# RP_INTERFACE_BOARD_V1.net
KiCad netlist of a schematic drawn in Altium Designer
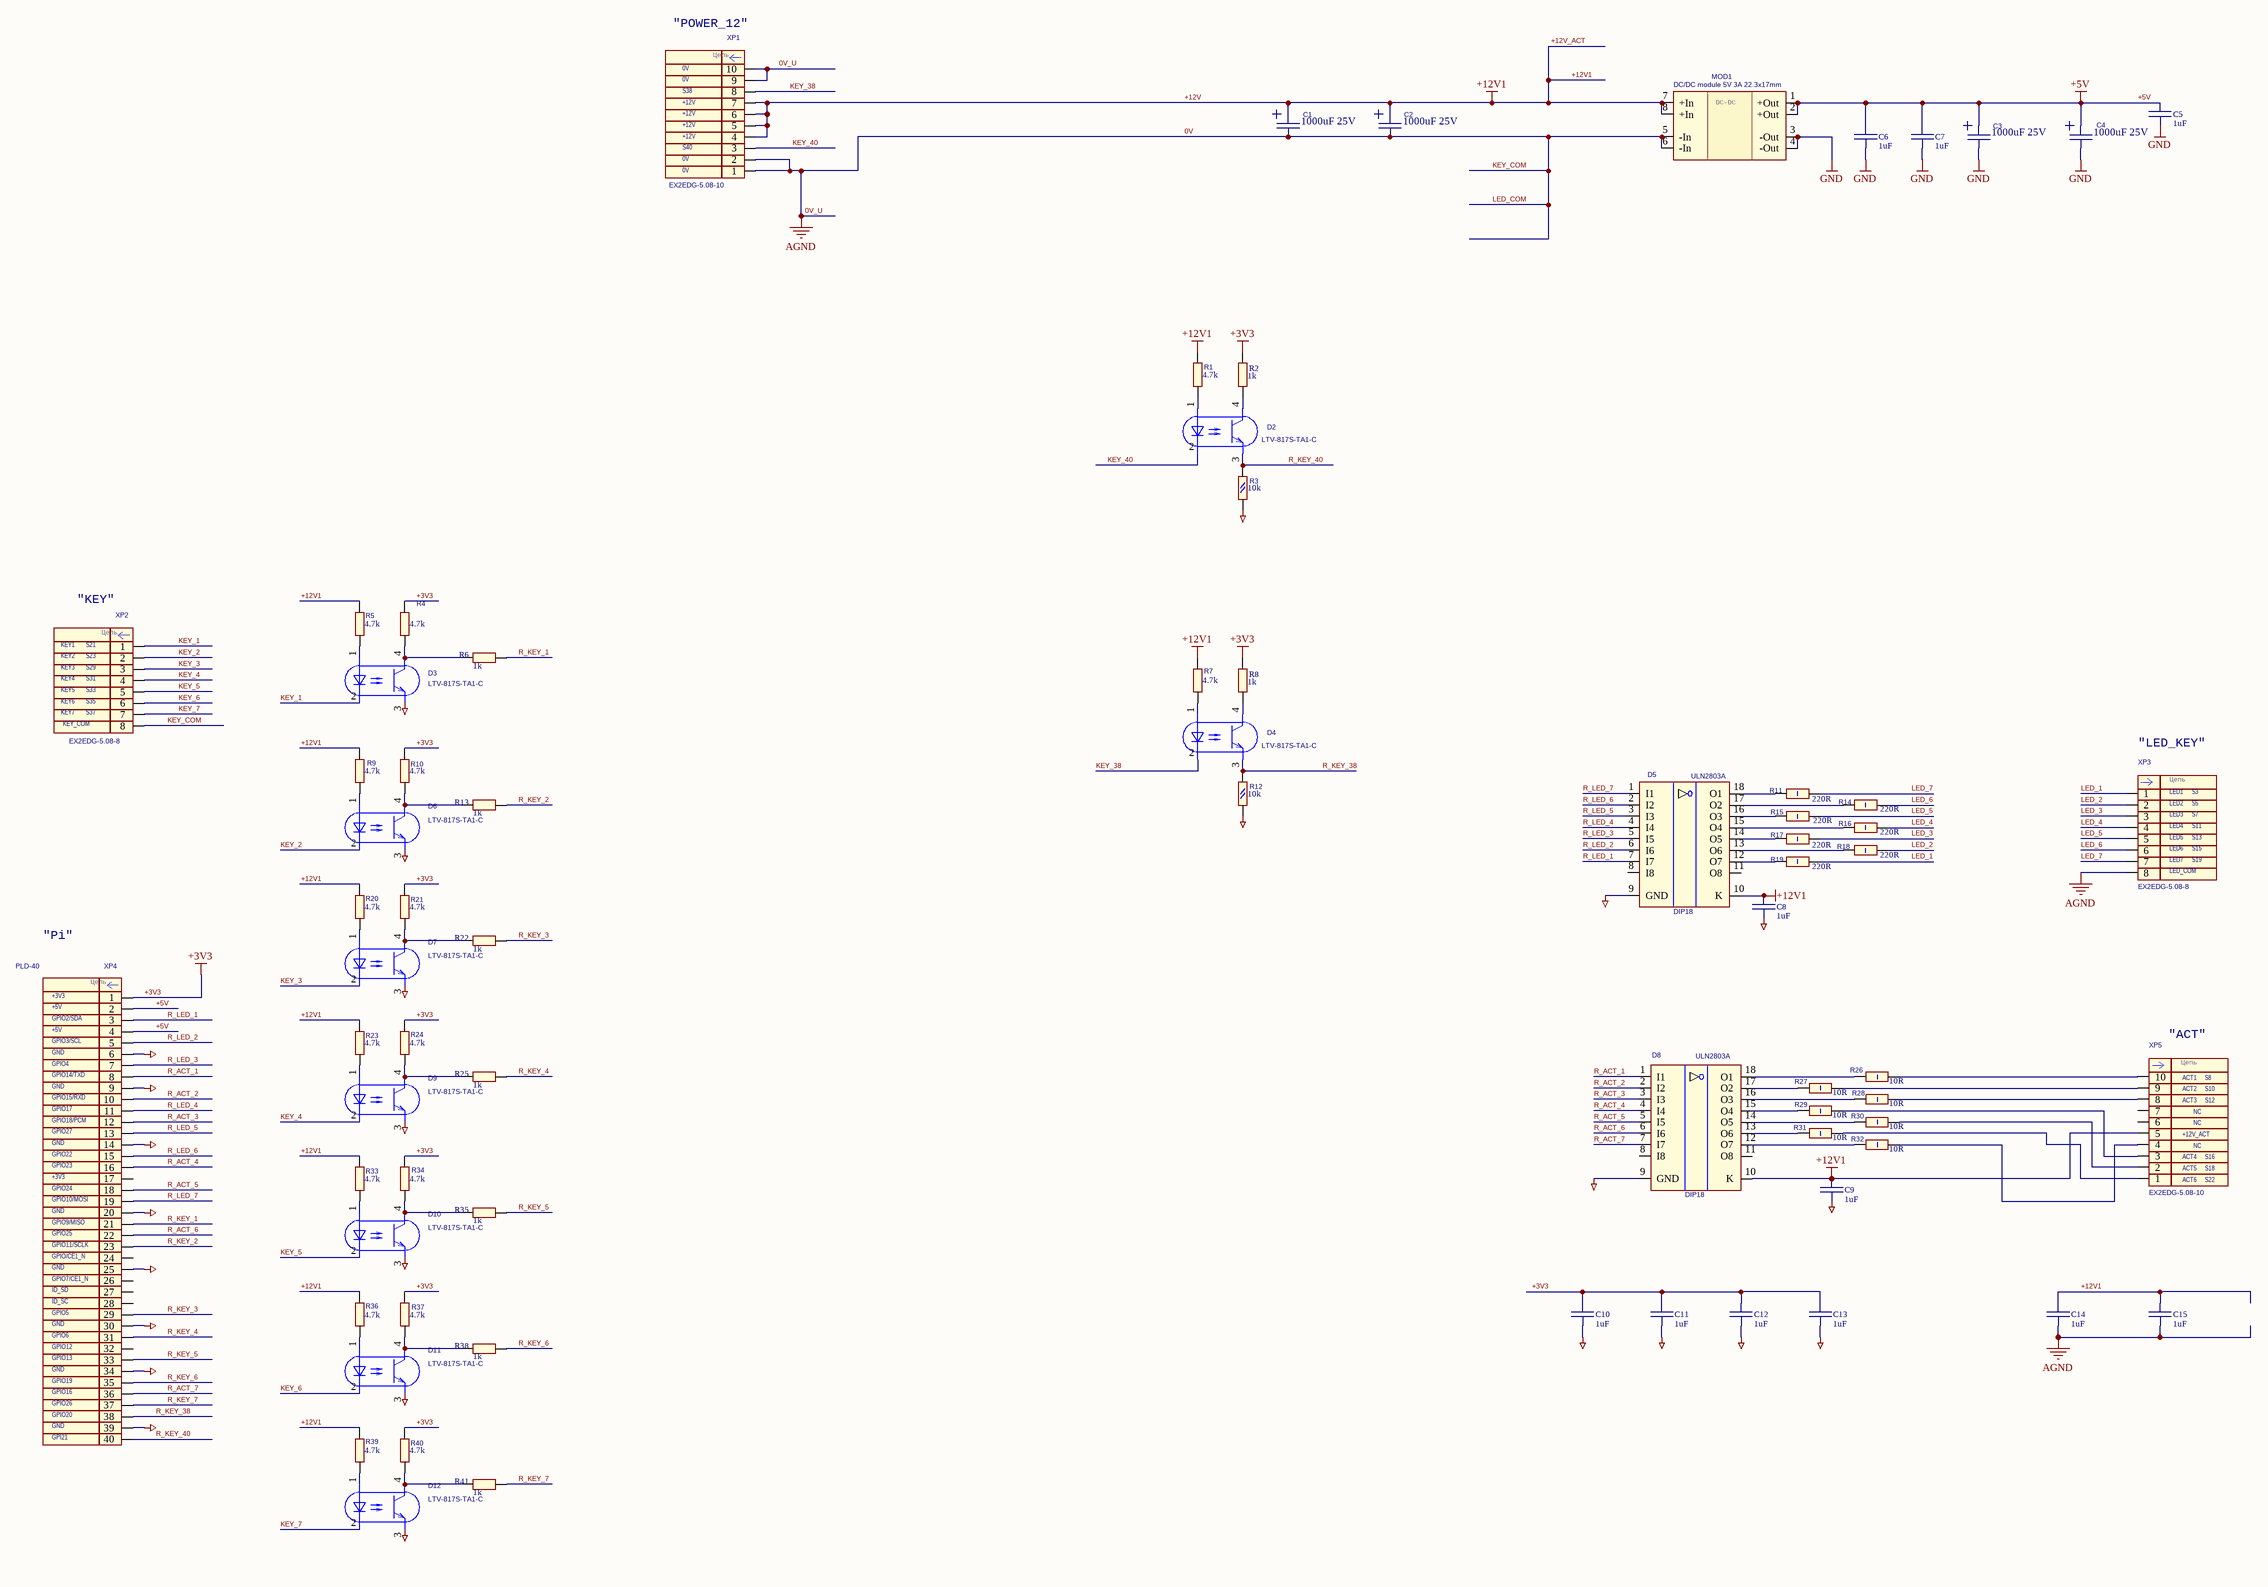
[diagram p0: RP_INTERFACE_BOARD_V1.SchDoc]

(export (version "E")
  (design (tool "Eeschema 10.0.6"))
  (components
    (comp (ref "C1")
      (value "EXR102M25B")
      (footprint "RADIAL 13X25")
      (description "1000uF 25V 13x21mm")
      (fields (field (name "ALTIUM_UNNAMED_1") "1000uF 25V"))
      (libsource (lib "*") (part "EXR102M25B"))
    )
    (comp (ref "C2")
      (value "EXR102M25B")
      (footprint "RADIAL 13X25")
      (description "1000uF 25V 13x21mm")
      (fields (field (name "ALTIUM_UNNAMED_1") "1000uF 25V"))
      (libsource (lib "RP_INTERFACE_BOARD") (part "EXR102M25B"))
    )
    (comp (ref "C3")
      (value "EXR102M25B")
      (footprint "RADIAL 13X25")
      (description "1000uF 25V 13x21mm")
      (fields (field (name "ALTIUM_UNNAMED_1") "1000uF 25V"))
      (libsource (lib "RP_INTERFACE_BOARD") (part "EXR102M25B"))
    )
    (comp (ref "C4")
      (value "EXR102M25B")
      (footprint "RADIAL 13X25")
      (description "1000uF 25V 13x21mm")
      (fields (field (name "ALTIUM_UNNAMED_1") "1000uF 25V"))
      (libsource (lib "RP_INTERFACE_BOARD") (part "EXR102M25B"))
    )
    (comp (ref "C5")
      (value "C0805, 1uF, 50V, X7R")
      (footprint "C0805")
      (fields (field (name "ALTIUM_UNNAMED_1") "1uF"))
      (libsource (lib "CAPACITORS") (part "C0805, 1uF, 50V, X7R"))
    )
    (comp (ref "C6")
      (value "C0805, 1uF, 50V, X7R")
      (footprint "C0805")
      (fields (field (name "ALTIUM_UNNAMED_1") "1uF"))
      (libsource (lib "CAPACITORS") (part "C0805, 1uF, 50V, X7R"))
    )
    (comp (ref "C7")
      (value "C0805, 1uF, 50V, X7R")
      (footprint "C0805")
      (fields (field (name "ALTIUM_UNNAMED_1") "1uF"))
      (libsource (lib "CAPACITORS") (part "C0805, 1uF, 50V, X7R"))
    )
    (comp (ref "C8")
      (value "C0805, 1uF, 50V, X7R")
      (footprint "C0805")
      (fields (field (name "ALTIUM_UNNAMED_1") "1uF"))
      (libsource (lib "CAPACITORS") (part "C0805, 1uF, 50V, X7R"))
    )
    (comp (ref "C9")
      (value "C0805, 1uF, 50V, X7R")
      (footprint "C0805")
      (fields (field (name "ALTIUM_UNNAMED_1") "1uF"))
      (libsource (lib "CAPACITORS") (part "C0805, 1uF, 50V, X7R"))
    )
    (comp (ref "C10")
      (value "C0805, 1uF, 50V, X7R")
      (footprint "C0805")
      (fields (field (name "ALTIUM_UNNAMED_1") "1uF"))
      (libsource (lib "CAPACITORS") (part "C0805, 1uF, 50V, X7R"))
    )
    (comp (ref "C11")
      (value "C0805, 1uF, 50V, X7R")
      (footprint "C0805")
      (fields (field (name "ALTIUM_UNNAMED_1") "1uF"))
      (libsource (lib "CAPACITORS") (part "C0805, 1uF, 50V, X7R"))
    )
    (comp (ref "C12")
      (value "C0805, 1uF, 50V, X7R")
      (footprint "C0805")
      (fields (field (name "ALTIUM_UNNAMED_1") "1uF"))
      (libsource (lib "CAPACITORS") (part "C0805, 1uF, 50V, X7R"))
    )
    (comp (ref "C13")
      (value "C0805, 1uF, 50V, X7R")
      (footprint "C0805")
      (fields (field (name "ALTIUM_UNNAMED_1") "1uF"))
      (libsource (lib "CAPACITORS") (part "C0805, 1uF, 50V, X7R"))
    )
    (comp (ref "C14")
      (value "C0805, 1uF, 50V, X7R")
      (footprint "C0805")
      (fields (field (name "ALTIUM_UNNAMED_1") "1uF"))
      (libsource (lib "CAPACITORS") (part "C0805, 1uF, 50V, X7R"))
    )
    (comp (ref "C15")
      (value "C0805, 1uF, 50V, X7R")
      (footprint "C0805")
      (fields (field (name "ALTIUM_UNNAMED_1") "1uF"))
      (libsource (lib "CAPACITORS") (part "C0805, 1uF, 50V, X7R"))
    )
    (comp (ref "D2")
      (value "LTV-817S-TA1-C")
      (footprint "SOIC4")
      (description "Optoisolator Transistor Output 5000Vrms 1 Channel 4-SMD")
      (libsource (lib "RP_INTERFACE_BOARD") (part "LTV-817S-TA1-C"))
    )
    (comp (ref "D3")
      (value "LTV-817S-TA1-C")
      (footprint "SOIC4")
      (description "Optoisolator Transistor Output 5000Vrms 1 Channel 4-SMD")
      (libsource (lib "RP_INTERFACE_BOARD") (part "LTV-817S-TA1-C"))
    )
    (comp (ref "D4")
      (value "LTV-817S-TA1-C")
      (footprint "SOIC4")
      (description "Optoisolator Transistor Output 5000Vrms 1 Channel 4-SMD")
      (libsource (lib "RP_INTERFACE_BOARD") (part "LTV-817S-TA1-C"))
    )
    (comp (ref "D5")
      (value "ULN2803A")
      (footprint "DIP18_DIP762W46P254L2286H533Q18P")
      (description "Eight Darlington array, DIP-18")
      (fields (field (name "KORPUS3") "DIP18"))
      (libsource (lib "RP_INTERFACE_BOARD") (part "ULN2803A"))
    )
    (comp (ref "D6")
      (value "LTV-817S-TA1-C")
      (footprint "SOIC4")
      (description "Optoisolator Transistor Output 5000Vrms 1 Channel 4-SMD")
      (libsource (lib "RP_INTERFACE_BOARD") (part "LTV-817S-TA1-C"))
    )
    (comp (ref "D7")
      (value "LTV-817S-TA1-C")
      (footprint "SOIC4")
      (description "Optoisolator Transistor Output 5000Vrms 1 Channel 4-SMD")
      (libsource (lib "RP_INTERFACE_BOARD") (part "LTV-817S-TA1-C"))
    )
    (comp (ref "D8")
      (value "ULN2803A")
      (footprint "DIP18_DIP762W46P254L2286H533Q18P")
      (description "Eight Darlington array, DIP-18")
      (fields (field (name "KORPUS3") "DIP18"))
      (libsource (lib "RP_INTERFACE_BOARD") (part "ULN2803A"))
    )
    (comp (ref "D9")
      (value "LTV-817S-TA1-C")
      (footprint "SOIC4")
      (description "Optoisolator Transistor Output 5000Vrms 1 Channel 4-SMD")
      (libsource (lib "RP_INTERFACE_BOARD") (part "LTV-817S-TA1-C"))
    )
    (comp (ref "D10")
      (value "LTV-817S-TA1-C")
      (footprint "SOIC4")
      (description "Optoisolator Transistor Output 5000Vrms 1 Channel 4-SMD")
      (libsource (lib "RP_INTERFACE_BOARD") (part "LTV-817S-TA1-C"))
    )
    (comp (ref "D11")
      (value "LTV-817S-TA1-C")
      (footprint "SOIC4")
      (description "Optoisolator Transistor Output 5000Vrms 1 Channel 4-SMD")
      (libsource (lib "RP_INTERFACE_BOARD") (part "LTV-817S-TA1-C"))
    )
    (comp (ref "D12")
      (value "LTV-817S-TA1-C")
      (footprint "SOIC4")
      (description "Optoisolator Transistor Output 5000Vrms 1 Channel 4-SMD")
      (libsource (lib "RP_INTERFACE_BOARD") (part "LTV-817S-TA1-C"))
    )
    (comp (ref "MOD1")
      (value "DC/DC module 5V 3A 22.3x17mm")
      (footprint "DC_DC_module 5V, 17x22.3mm")
      (libsource (lib "*") (part "DC/DC module 5V 3A 22.3x17mm"))
    )
    (comp (ref "R1")
      (value "4.7k")
      (footprint "R0805")
      (description "R0805, 4.7k, 5%")
      (libsource (lib "RP_INTERFACE_BOARD") (part "R0805, 4.7k, 5%"))
    )
    (comp (ref "R2")
      (value "R0805, 1k, 5%")
      (footprint "R0805")
      (fields (field (name "ALTIUM_UNNAMED_1") "1k"))
      (libsource (lib "") (part "R0805, 1k, 5%_1"))
    )
    (comp (ref "R3")
      (value "10k")
      (footprint "R0805")
      (description "R0805, 10k, 5%")
      (libsource (lib "RP_INTERFACE_BOARD") (part "R0805, 10k, 5%"))
    )
    (comp (ref "R4")
      (value "4.7k")
      (footprint "R0805")
      (description "R0805, 4.7k, 5%")
      (libsource (lib "RP_INTERFACE_BOARD") (part "R0805, 4.7k, 5%"))
    )
    (comp (ref "R5")
      (value "4.7k")
      (footprint "R0805")
      (description "R0805, 4.7k, 5%")
      (libsource (lib "RP_INTERFACE_BOARD") (part "R0805, 4.7k, 5%"))
    )
    (comp (ref "R6")
      (value "R0805, 1k, 5%")
      (footprint "R0805")
      (fields (field (name "ALTIUM_UNNAMED_1") "1k"))
      (libsource (lib "RP_INTERFACE_BOARD") (part "R0805, 1k, 5%"))
    )
    (comp (ref "R7")
      (value "4.7k")
      (footprint "R0805")
      (description "R0805, 4.7k, 5%")
      (libsource (lib "RP_INTERFACE_BOARD") (part "R0805, 4.7k, 5%"))
    )
    (comp (ref "R8")
      (value "R0805, 1k, 5%")
      (footprint "R0805")
      (fields (field (name "ALTIUM_UNNAMED_1") "1k"))
      (libsource (lib "") (part "R0805, 1k, 5%_1"))
    )
    (comp (ref "R9")
      (value "4.7k")
      (footprint "R0805")
      (description "R0805, 4.7k, 5%")
      (libsource (lib "RP_INTERFACE_BOARD") (part "R0805, 4.7k, 5%"))
    )
    (comp (ref "R10")
      (value "4.7k")
      (footprint "R0805")
      (description "R0805, 4.7k, 5%")
      (libsource (lib "RP_INTERFACE_BOARD") (part "R0805, 4.7k, 5%"))
    )
    (comp (ref "R11")
      (value "R1206, 220R, 5%")
      (footprint "R1206")
      (fields (field (name "ALTIUM_UNNAMED_1") "220R"))
      (libsource (lib "RP_INTERFACE_BOARD") (part "R1206, 220R, 5%"))
    )
    (comp (ref "R12")
      (value "10k")
      (footprint "R0805")
      (description "R0805, 10k, 5%")
      (libsource (lib "RP_INTERFACE_BOARD") (part "R0805, 10k, 5%"))
    )
    (comp (ref "R13")
      (value "R0805, 1k, 5%")
      (footprint "R0805")
      (fields (field (name "ALTIUM_UNNAMED_1") "1k"))
      (libsource (lib "RP_INTERFACE_BOARD") (part "R0805, 1k, 5%"))
    )
    (comp (ref "R14")
      (value "R1206, 220R, 5%")
      (footprint "R1206")
      (fields (field (name "ALTIUM_UNNAMED_1") "220R"))
      (libsource (lib "RP_INTERFACE_BOARD") (part "R1206, 220R, 5%"))
    )
    (comp (ref "R15")
      (value "R1206, 220R, 5%")
      (footprint "R1206")
      (fields (field (name "ALTIUM_UNNAMED_1") "220R"))
      (libsource (lib "RP_INTERFACE_BOARD") (part "R1206, 220R, 5%"))
    )
    (comp (ref "R16")
      (value "R1206, 220R, 5%")
      (footprint "R1206")
      (fields (field (name "ALTIUM_UNNAMED_1") "220R"))
      (libsource (lib "RP_INTERFACE_BOARD") (part "R1206, 220R, 5%"))
    )
    (comp (ref "R17")
      (value "R1206, 220R, 5%")
      (footprint "R1206")
      (fields (field (name "ALTIUM_UNNAMED_1") "220R"))
      (libsource (lib "RP_INTERFACE_BOARD") (part "R1206, 220R, 5%"))
    )
    (comp (ref "R18")
      (value "R1206, 220R, 5%")
      (footprint "R1206")
      (fields (field (name "ALTIUM_UNNAMED_1") "220R"))
      (libsource (lib "RP_INTERFACE_BOARD") (part "R1206, 220R, 5%"))
    )
    (comp (ref "R19")
      (value "R1206, 220R, 5%")
      (footprint "R1206")
      (fields (field (name "ALTIUM_UNNAMED_1") "220R"))
      (libsource (lib "RP_INTERFACE_BOARD") (part "R1206, 220R, 5%"))
    )
    (comp (ref "R20")
      (value "4.7k")
      (footprint "R0805")
      (description "R0805, 4.7k, 5%")
      (libsource (lib "RP_INTERFACE_BOARD") (part "R0805, 4.7k, 5%"))
    )
    (comp (ref "R21")
      (value "4.7k")
      (footprint "R0805")
      (description "R0805, 4.7k, 5%")
      (libsource (lib "RP_INTERFACE_BOARD") (part "R0805, 4.7k, 5%"))
    )
    (comp (ref "R22")
      (value "R0805, 1k, 5%")
      (footprint "R0805")
      (fields (field (name "ALTIUM_UNNAMED_1") "1k"))
      (libsource (lib "RP_INTERFACE_BOARD") (part "R0805, 1k, 5%"))
    )
    (comp (ref "R23")
      (value "4.7k")
      (footprint "R0805")
      (description "R0805, 4.7k, 5%")
      (libsource (lib "RP_INTERFACE_BOARD") (part "R0805, 4.7k, 5%"))
    )
    (comp (ref "R24")
      (value "4.7k")
      (footprint "R0805")
      (description "R0805, 4.7k, 5%")
      (libsource (lib "RP_INTERFACE_BOARD") (part "R0805, 4.7k, 5%"))
    )
    (comp (ref "R25")
      (value "R0805, 1k, 5%")
      (footprint "R0805")
      (fields (field (name "ALTIUM_UNNAMED_1") "1k"))
      (libsource (lib "RP_INTERFACE_BOARD") (part "R0805, 1k, 5%"))
    )
    (comp (ref "R26")
      (value "R1206, 10R, 5%")
      (footprint "R1206")
      (fields (field (name "ALTIUM_UNNAMED_1") "10R"))
      (libsource (lib "*") (part "R1206, 10R, 5%"))
    )
    (comp (ref "R27")
      (value "R1206, 10R, 5%")
      (footprint "R1206")
      (fields (field (name "ALTIUM_UNNAMED_1") "10R"))
      (libsource (lib "*") (part "R1206, 10R, 5%"))
    )
    (comp (ref "R28")
      (value "R1206, 10R, 5%")
      (footprint "R1206")
      (fields (field (name "ALTIUM_UNNAMED_1") "10R"))
      (libsource (lib "*") (part "R1206, 10R, 5%"))
    )
    (comp (ref "R29")
      (value "R1206, 10R, 5%")
      (footprint "R1206")
      (fields (field (name "ALTIUM_UNNAMED_1") "10R"))
      (libsource (lib "*") (part "R1206, 10R, 5%"))
    )
    (comp (ref "R30")
      (value "R1206, 10R, 5%")
      (footprint "R1206")
      (fields (field (name "ALTIUM_UNNAMED_1") "10R"))
      (libsource (lib "*") (part "R1206, 10R, 5%"))
    )
    (comp (ref "R31")
      (value "R1206, 10R, 5%")
      (footprint "R1206")
      (fields (field (name "ALTIUM_UNNAMED_1") "10R"))
      (libsource (lib "*") (part "R1206, 10R, 5%"))
    )
    (comp (ref "R32")
      (value "R1206, 10R, 5%")
      (footprint "R1206")
      (fields (field (name "ALTIUM_UNNAMED_1") "10R"))
      (libsource (lib "*") (part "R1206, 10R, 5%"))
    )
    (comp (ref "R33")
      (value "4.7k")
      (footprint "R0805")
      (description "R0805, 4.7k, 5%")
      (libsource (lib "RP_INTERFACE_BOARD") (part "R0805, 4.7k, 5%"))
    )
    (comp (ref "R34")
      (value "4.7k")
      (footprint "R0805")
      (description "R0805, 4.7k, 5%")
      (libsource (lib "RP_INTERFACE_BOARD") (part "R0805, 4.7k, 5%"))
    )
    (comp (ref "R35")
      (value "R0805, 1k, 5%")
      (footprint "R0805")
      (fields (field (name "ALTIUM_UNNAMED_1") "1k"))
      (libsource (lib "RP_INTERFACE_BOARD") (part "R0805, 1k, 5%"))
    )
    (comp (ref "R36")
      (value "4.7k")
      (footprint "R0805")
      (description "R0805, 4.7k, 5%")
      (libsource (lib "RP_INTERFACE_BOARD") (part "R0805, 4.7k, 5%"))
    )
    (comp (ref "R37")
      (value "4.7k")
      (footprint "R0805")
      (description "R0805, 4.7k, 5%")
      (libsource (lib "RP_INTERFACE_BOARD") (part "R0805, 4.7k, 5%"))
    )
    (comp (ref "R38")
      (value "R0805, 1k, 5%")
      (footprint "R0805")
      (fields (field (name "ALTIUM_UNNAMED_1") "1k"))
      (libsource (lib "RP_INTERFACE_BOARD") (part "R0805, 1k, 5%"))
    )
    (comp (ref "R39")
      (value "4.7k")
      (footprint "R0805")
      (description "R0805, 4.7k, 5%")
      (libsource (lib "RP_INTERFACE_BOARD") (part "R0805, 4.7k, 5%"))
    )
    (comp (ref "R40")
      (value "4.7k")
      (footprint "R0805")
      (description "R0805, 4.7k, 5%")
      (libsource (lib "RP_INTERFACE_BOARD") (part "R0805, 4.7k, 5%"))
    )
    (comp (ref "R41")
      (value "R0805, 1k, 5%")
      (footprint "R0805")
      (fields (field (name "ALTIUM_UNNAMED_1") "1k"))
      (libsource (lib "RP_INTERFACE_BOARD") (part "R0805, 1k, 5%"))
    )
    (comp (ref "XP1")
      (value "EX2EDG-5.08-10")
      (footprint "5P08-10N")
      (libsource (lib "") (part "EX2EDG-5_0.08-10_1"))
    )
    (comp (ref "XP2")
      (value "EX2EDG-5.08-8")
      (footprint "5P08-8N")
      (libsource (lib "") (part "EX2EDG-5.08-8_1"))
    )
    (comp (ref "XP3")
      (value "EX2EDG-5.08-8")
      (footprint "5P08-8N")
      (libsource (lib "*") (part "EX2EDG-5.08-8"))
    )
    (comp (ref "XP4")
      (value "PLD-40")
      (footprint "PLD-40")
      (description "PLD-40, вилка штыревая 2.54мм 2x20 прямая")
      (libsource (lib "*") (part "PLD-40"))
    )
    (comp (ref "XP5")
      (value "EX2EDG-5.08-10")
      (footprint "5P08-10N")
      (libsource (lib "*") (part "EX2EDG-5_0.08-10"))
    )
  )
  (nets
    (net (code "1") (name "+3V3") (class "Default")
      (node (ref "C10") (pin "1") (pintype "passive"))
      (node (ref "C11") (pin "1") (pintype "passive"))
      (node (ref "C12") (pin "1") (pintype "passive"))
      (node (ref "C13") (pin "1") (pintype "passive"))
      (node (ref "R10") (pin "1") (pinfunction "1_1") (pintype "passive"))
      (node (ref "R2") (pin "1") (pinfunction "1_1") (pintype "passive"))
      (node (ref "R21") (pin "1") (pinfunction "1_1") (pintype "passive"))
      (node (ref "R24") (pin "1") (pinfunction "1_1") (pintype "passive"))
      (node (ref "R34") (pin "1") (pinfunction "1_1") (pintype "passive"))
      (node (ref "R37") (pin "1") (pinfunction "1_1") (pintype "passive"))
      (node (ref "R4") (pin "1") (pinfunction "1_1") (pintype "passive"))
      (node (ref "R40") (pin "1") (pinfunction "1_1") (pintype "passive"))
      (node (ref "R8") (pin "1") (pinfunction "1_1") (pintype "passive"))
      (node (ref "XP4") (pin "1") (pinfunction "1_1") (pintype "passive"))
    )
    (net (code "2") (name "+5V") (class "Default")
      (node (ref "C3") (pin "2") (pintype "passive"))
      (node (ref "C4") (pin "2") (pintype "passive"))
      (node (ref "C5") (pin "1") (pintype "passive"))
      (node (ref "C6") (pin "1") (pintype "passive"))
      (node (ref "C7") (pin "1") (pintype "passive"))
      (node (ref "MOD1") (pin "1") (pinfunction "+Out_1") (pintype "power_in"))
      (node (ref "MOD1") (pin "2") (pinfunction "+Out_2") (pintype "power_in"))
      (node (ref "XP4") (pin "2") (pinfunction "2_2") (pintype "passive"))
      (node (ref "XP4") (pin "4") (pinfunction "4_4") (pintype "passive"))
    )
    (net (code "3") (name "+12V1") (class "Default")
      (node (ref "C1") (pin "2") (pintype "passive"))
      (node (ref "C14") (pin "1") (pintype "passive"))
      (node (ref "C15") (pin "1") (pintype "passive"))
      (node (ref "C2") (pin "2") (pintype "passive"))
      (node (ref "C8") (pin "1") (pintype "passive"))
      (node (ref "C9") (pin "1") (pintype "passive"))
      (node (ref "D5") (pin "10") (pinfunction "K_10") (pintype "power_in"))
      (node (ref "D8") (pin "10") (pinfunction "K_10") (pintype "power_in"))
      (node (ref "MOD1") (pin "7") (pinfunction "+In_7") (pintype "power_in"))
      (node (ref "MOD1") (pin "8") (pinfunction "+In_8") (pintype "power_in"))
      (node (ref "R1") (pin "1") (pinfunction "1_1") (pintype "passive"))
      (node (ref "R20") (pin "1") (pinfunction "1_1") (pintype "passive"))
      (node (ref "R23") (pin "1") (pinfunction "1_1") (pintype "passive"))
      (node (ref "R33") (pin "1") (pinfunction "1_1") (pintype "passive"))
      (node (ref "R36") (pin "1") (pinfunction "1_1") (pintype "passive"))
      (node (ref "R39") (pin "1") (pinfunction "1_1") (pintype "passive"))
      (node (ref "R5") (pin "1") (pinfunction "1_1") (pintype "passive"))
      (node (ref "R7") (pin "1") (pinfunction "1_1") (pintype "passive"))
      (node (ref "R9") (pin "1") (pinfunction "1_1") (pintype "passive"))
      (node (ref "XP1") (pin "4") (pinfunction "4_4") (pintype "passive"))
      (node (ref "XP1") (pin "5") (pinfunction "5_5") (pintype "passive"))
      (node (ref "XP1") (pin "6") (pinfunction "6_6") (pintype "passive"))
      (node (ref "XP1") (pin "7") (pinfunction "7_7") (pintype "passive"))
      (node (ref "XP5") (pin "5") (pinfunction "5_5") (pintype "passive"))
    )
    (net (code "4") (name "/KEY_1") (class "Default")
      (node (ref "D3") (pin "2") (pinfunction "2_2") (pintype "passive"))
      (node (ref "XP2") (pin "1") (pinfunction "1_1") (pintype "passive"))
    )
    (net (code "5") (name "/KEY_2") (class "Default")
      (node (ref "D6") (pin "2") (pinfunction "2_2") (pintype "passive"))
      (node (ref "XP2") (pin "2") (pinfunction "2_2") (pintype "passive"))
    )
    (net (code "6") (name "/KEY_3") (class "Default")
      (node (ref "D7") (pin "2") (pinfunction "2_2") (pintype "passive"))
      (node (ref "XP2") (pin "3") (pinfunction "3_3") (pintype "passive"))
    )
    (net (code "7") (name "/KEY_4") (class "Default")
      (node (ref "D9") (pin "2") (pinfunction "2_2") (pintype "passive"))
      (node (ref "XP2") (pin "4") (pinfunction "4_4") (pintype "passive"))
    )
    (net (code "8") (name "/KEY_5") (class "Default")
      (node (ref "D10") (pin "2") (pinfunction "2_2") (pintype "passive"))
      (node (ref "XP2") (pin "5") (pinfunction "5_5") (pintype "passive"))
    )
    (net (code "9") (name "/KEY_6") (class "Default")
      (node (ref "D11") (pin "2") (pinfunction "2_2") (pintype "passive"))
      (node (ref "XP2") (pin "6") (pinfunction "6_6") (pintype "passive"))
    )
    (net (code "10") (name "/KEY_7") (class "Default")
      (node (ref "D12") (pin "2") (pinfunction "2_2") (pintype "passive"))
      (node (ref "XP2") (pin "7") (pinfunction "7_7") (pintype "passive"))
    )
    (net (code "11") (name "/KEY_38") (class "Default")
      (node (ref "D4") (pin "2") (pinfunction "2_2") (pintype "passive"))
      (node (ref "XP1") (pin "8") (pinfunction "8_8") (pintype "passive"))
    )
    (net (code "12") (name "/KEY_40") (class "Default")
      (node (ref "D2") (pin "2") (pinfunction "2_2") (pintype "passive"))
      (node (ref "XP1") (pin "3") (pinfunction "3_3") (pintype "passive"))
    )
    (net (code "13") (name "/LED_1") (class "Default")
      (node (ref "R19") (pin "2") (pinfunction "2_2") (pintype "passive"))
      (node (ref "XP3") (pin "1") (pinfunction "1_1") (pintype "passive"))
    )
    (net (code "14") (name "/LED_2") (class "Default")
      (node (ref "R18") (pin "2") (pinfunction "2_2") (pintype "passive"))
      (node (ref "XP3") (pin "2") (pinfunction "2_2") (pintype "passive"))
    )
    (net (code "15") (name "/LED_3") (class "Default")
      (node (ref "R17") (pin "2") (pinfunction "2_2") (pintype "passive"))
      (node (ref "XP3") (pin "3") (pinfunction "3_3") (pintype "passive"))
    )
    (net (code "16") (name "/LED_4") (class "Default")
      (node (ref "R16") (pin "2") (pinfunction "2_2") (pintype "passive"))
      (node (ref "XP3") (pin "4") (pinfunction "4_4") (pintype "passive"))
    )
    (net (code "17") (name "/LED_5") (class "Default")
      (node (ref "R15") (pin "2") (pinfunction "2_2") (pintype "passive"))
      (node (ref "XP3") (pin "5") (pinfunction "5_5") (pintype "passive"))
    )
    (net (code "18") (name "/LED_6") (class "Default")
      (node (ref "R14") (pin "2") (pinfunction "2_2") (pintype "passive"))
      (node (ref "XP3") (pin "6") (pinfunction "6_6") (pintype "passive"))
    )
    (net (code "19") (name "/LED_7") (class "Default")
      (node (ref "R11") (pin "2") (pinfunction "2_2") (pintype "passive"))
      (node (ref "XP3") (pin "7") (pinfunction "7_7") (pintype "passive"))
    )
    (net (code "20") (name "/R_ACT_1") (class "Default")
      (node (ref "D8") (pin "1") (pinfunction "I1_1") (pintype "passive"))
      (node (ref "XP4") (pin "8") (pinfunction "8_8") (pintype "passive"))
    )
    (net (code "21") (name "/R_ACT_2") (class "Default")
      (node (ref "D8") (pin "2") (pinfunction "I2_2") (pintype "passive"))
      (node (ref "XP4") (pin "10") (pinfunction "10_10") (pintype "passive"))
    )
    (net (code "22") (name "/R_ACT_3") (class "Default")
      (node (ref "D8") (pin "3") (pinfunction "I3_3") (pintype "passive"))
      (node (ref "XP4") (pin "12") (pinfunction "12_12") (pintype "passive"))
    )
    (net (code "23") (name "/R_ACT_4") (class "Default")
      (node (ref "D8") (pin "4") (pinfunction "I4_4") (pintype "passive"))
      (node (ref "XP4") (pin "16") (pinfunction "16_16") (pintype "passive"))
    )
    (net (code "24") (name "/R_ACT_5") (class "Default")
      (node (ref "D8") (pin "5") (pinfunction "I5_5") (pintype "passive"))
      (node (ref "XP4") (pin "18") (pinfunction "18_18") (pintype "passive"))
    )
    (net (code "25") (name "/R_ACT_6") (class "Default")
      (node (ref "D8") (pin "6") (pinfunction "I6_6") (pintype "passive"))
      (node (ref "XP4") (pin "22") (pinfunction "22_22") (pintype "passive"))
    )
    (net (code "26") (name "/R_ACT_7") (class "Default")
      (node (ref "D8") (pin "7") (pinfunction "I7_7") (pintype "passive"))
      (node (ref "XP4") (pin "36") (pinfunction "36_36") (pintype "passive"))
    )
    (net (code "27") (name "/R_KEY_1") (class "Default")
      (node (ref "R6") (pin "1") (pinfunction "1_1") (pintype "passive"))
      (node (ref "XP4") (pin "21") (pinfunction "21_21") (pintype "passive"))
    )
    (net (code "28") (name "/R_KEY_2") (class "Default")
      (node (ref "R13") (pin "1") (pinfunction "1_1") (pintype "passive"))
      (node (ref "XP4") (pin "23") (pinfunction "23_23") (pintype "passive"))
    )
    (net (code "29") (name "/R_KEY_3") (class "Default")
      (node (ref "R22") (pin "1") (pinfunction "1_1") (pintype "passive"))
      (node (ref "XP4") (pin "29") (pinfunction "29_29") (pintype "passive"))
    )
    (net (code "30") (name "/R_KEY_4") (class "Default")
      (node (ref "R25") (pin "1") (pinfunction "1_1") (pintype "passive"))
      (node (ref "XP4") (pin "31") (pinfunction "31_31") (pintype "passive"))
    )
    (net (code "31") (name "/R_KEY_5") (class "Default")
      (node (ref "R35") (pin "1") (pinfunction "1_1") (pintype "passive"))
      (node (ref "XP4") (pin "33") (pinfunction "33_33") (pintype "passive"))
    )
    (net (code "32") (name "/R_KEY_6") (class "Default")
      (node (ref "R38") (pin "1") (pinfunction "1_1") (pintype "passive"))
      (node (ref "XP4") (pin "35") (pinfunction "35_35") (pintype "passive"))
    )
    (net (code "33") (name "/R_KEY_7") (class "Default")
      (node (ref "R41") (pin "1") (pinfunction "1_1") (pintype "passive"))
      (node (ref "XP4") (pin "37") (pinfunction "37_37") (pintype "passive"))
    )
    (net (code "34") (name "/R_KEY_38") (class "Default")
      (node (ref "D4") (pin "3") (pinfunction "3_3") (pintype "passive"))
      (node (ref "R12") (pin "1") (pinfunction "1_1") (pintype "passive"))
      (node (ref "XP4") (pin "38") (pinfunction "38_38") (pintype "passive"))
    )
    (net (code "35") (name "/R_KEY_40") (class "Default")
      (node (ref "D2") (pin "3") (pinfunction "3_3") (pintype "passive"))
      (node (ref "R3") (pin "1") (pinfunction "1_1") (pintype "passive"))
      (node (ref "XP4") (pin "40") (pinfunction "40_40") (pintype "passive"))
    )
    (net (code "36") (name "/R_LED_1") (class "Default")
      (node (ref "D5") (pin "7") (pinfunction "I7_7") (pintype "passive"))
      (node (ref "XP4") (pin "3") (pinfunction "3_3") (pintype "passive"))
    )
    (net (code "37") (name "/R_LED_2") (class "Default")
      (node (ref "D5") (pin "6") (pinfunction "I6_6") (pintype "passive"))
      (node (ref "XP4") (pin "5") (pinfunction "5_5") (pintype "passive"))
    )
    (net (code "38") (name "/R_LED_3") (class "Default")
      (node (ref "D5") (pin "5") (pinfunction "I5_5") (pintype "passive"))
      (node (ref "XP4") (pin "7") (pinfunction "7_7") (pintype "passive"))
    )
    (net (code "39") (name "/R_LED_4") (class "Default")
      (node (ref "D5") (pin "4") (pinfunction "I4_4") (pintype "passive"))
      (node (ref "XP4") (pin "11") (pinfunction "11_11") (pintype "passive"))
    )
    (net (code "40") (name "/R_LED_5") (class "Default")
      (node (ref "D5") (pin "3") (pinfunction "I3_3") (pintype "passive"))
      (node (ref "XP4") (pin "13") (pinfunction "13_13") (pintype "passive"))
    )
    (net (code "41") (name "/R_LED_6") (class "Default")
      (node (ref "D5") (pin "2") (pinfunction "I2_2") (pintype "passive"))
      (node (ref "XP4") (pin "15") (pinfunction "15_15") (pintype "passive"))
    )
    (net (code "42") (name "/R_LED_7") (class "Default")
      (node (ref "D5") (pin "1") (pinfunction "I1_1") (pintype "passive"))
      (node (ref "XP4") (pin "19") (pinfunction "19_19") (pintype "passive"))
    )
    (net (code "43") (name "AGND") (class "Default")
      (node (ref "C1") (pin "1") (pintype "passive"))
      (node (ref "C14") (pin "2") (pintype "passive"))
      (node (ref "C15") (pin "2") (pintype "passive"))
      (node (ref "C2") (pin "1") (pintype "passive"))
      (node (ref "MOD1") (pin "5") (pinfunction "-In_5") (pintype "power_in"))
      (node (ref "MOD1") (pin "6") (pinfunction "-In_6") (pintype "power_in"))
      (node (ref "XP1") (pin "1") (pinfunction "1_1") (pintype "passive"))
      (node (ref "XP1") (pin "10") (pinfunction "10_10") (pintype "passive"))
      (node (ref "XP1") (pin "2") (pinfunction "2_2") (pintype "passive"))
      (node (ref "XP1") (pin "9") (pinfunction "9_9") (pintype "passive"))
      (node (ref "XP2") (pin "8") (pinfunction "8_8") (pintype "passive"))
      (node (ref "XP3") (pin "8") (pinfunction "8_8") (pintype "passive"))
    )
    (net (code "44") (name "GND") (class "Default")
      (node (ref "C10") (pin "2") (pintype "passive"))
      (node (ref "C11") (pin "2") (pintype "passive"))
      (node (ref "C12") (pin "2") (pintype "passive"))
      (node (ref "C13") (pin "2") (pintype "passive"))
      (node (ref "C3") (pin "1") (pintype "passive"))
      (node (ref "C4") (pin "1") (pintype "passive"))
      (node (ref "C5") (pin "2") (pintype "passive"))
      (node (ref "C6") (pin "2") (pintype "passive"))
      (node (ref "C7") (pin "2") (pintype "passive"))
      (node (ref "C8") (pin "2") (pintype "passive"))
      (node (ref "C9") (pin "2") (pintype "passive"))
      (node (ref "D10") (pin "3") (pinfunction "3_3") (pintype "passive"))
      (node (ref "D11") (pin "3") (pinfunction "3_3") (pintype "passive"))
      (node (ref "D12") (pin "3") (pinfunction "3_3") (pintype "passive"))
      (node (ref "D3") (pin "3") (pinfunction "3_3") (pintype "passive"))
      (node (ref "D5") (pin "9") (pinfunction "GND_9") (pintype "power_in"))
      (node (ref "D6") (pin "3") (pinfunction "3_3") (pintype "passive"))
      (node (ref "D7") (pin "3") (pinfunction "3_3") (pintype "passive"))
      (node (ref "D8") (pin "9") (pinfunction "GND_9") (pintype "power_in"))
      (node (ref "D9") (pin "3") (pinfunction "3_3") (pintype "passive"))
      (node (ref "MOD1") (pin "3") (pinfunction "-Out_3") (pintype "power_in"))
      (node (ref "MOD1") (pin "4") (pinfunction "-Out_4") (pintype "power_in"))
      (node (ref "R12") (pin "2") (pinfunction "2_2") (pintype "passive"))
      (node (ref "R3") (pin "2") (pinfunction "2_2") (pintype "passive"))
      (node (ref "XP4") (pin "14") (pinfunction "14_14") (pintype "passive"))
      (node (ref "XP4") (pin "20") (pinfunction "20_20") (pintype "passive"))
      (node (ref "XP4") (pin "25") (pinfunction "25_25") (pintype "passive"))
      (node (ref "XP4") (pin "30") (pinfunction "30_30") (pintype "passive"))
      (node (ref "XP4") (pin "34") (pinfunction "34_34") (pintype "passive"))
      (node (ref "XP4") (pin "39") (pinfunction "39_39") (pintype "passive"))
      (node (ref "XP4") (pin "6") (pinfunction "6_6") (pintype "passive"))
      (node (ref "XP4") (pin "9") (pinfunction "9_9") (pintype "passive"))
    )
    (net (code "45") (name "Net-(D2-Pad1)") (class "Default")
      (node (ref "D2") (pin "1") (pinfunction "1_1") (pintype "passive"))
      (node (ref "R1") (pin "2") (pinfunction "2_2") (pintype "passive"))
    )
    (net (code "46") (name "Net-(D2-Pad4)") (class "Default")
      (node (ref "D2") (pin "4") (pinfunction "4_4") (pintype "passive"))
      (node (ref "R2") (pin "2") (pinfunction "2_2") (pintype "passive"))
    )
    (net (code "47") (name "Net-(D3-Pad1)") (class "Default")
      (node (ref "D3") (pin "1") (pinfunction "1_1") (pintype "passive"))
      (node (ref "R5") (pin "2") (pinfunction "2_2") (pintype "passive"))
    )
    (net (code "48") (name "Net-(D3-Pad4)") (class "Default")
      (node (ref "D3") (pin "4") (pinfunction "4_4") (pintype "passive"))
      (node (ref "R4") (pin "2") (pinfunction "2_2") (pintype "passive"))
      (node (ref "R6") (pin "2") (pinfunction "2_2") (pintype "passive"))
    )
    (net (code "49") (name "Net-(D4-Pad1)") (class "Default")
      (node (ref "D4") (pin "1") (pinfunction "1_1") (pintype "passive"))
      (node (ref "R7") (pin "2") (pinfunction "2_2") (pintype "passive"))
    )
    (net (code "50") (name "Net-(D4-Pad4)") (class "Default")
      (node (ref "D4") (pin "4") (pinfunction "4_4") (pintype "passive"))
      (node (ref "R8") (pin "2") (pinfunction "2_2") (pintype "passive"))
    )
    (net (code "51") (name "Net-(D5-O1)") (class "Default")
      (node (ref "D5") (pin "18") (pinfunction "O1_18") (pintype "passive"))
      (node (ref "R11") (pin "1") (pinfunction "1_1") (pintype "passive"))
    )
    (net (code "52") (name "Net-(D5-O2)") (class "Default")
      (node (ref "D5") (pin "17") (pinfunction "O2_17") (pintype "passive"))
      (node (ref "R14") (pin "1") (pinfunction "1_1") (pintype "passive"))
    )
    (net (code "53") (name "Net-(D5-O3)") (class "Default")
      (node (ref "D5") (pin "16") (pinfunction "O3_16") (pintype "passive"))
      (node (ref "R15") (pin "1") (pinfunction "1_1") (pintype "passive"))
    )
    (net (code "54") (name "Net-(D5-O4)") (class "Default")
      (node (ref "D5") (pin "15") (pinfunction "O4_15") (pintype "passive"))
      (node (ref "R16") (pin "1") (pinfunction "1_1") (pintype "passive"))
    )
    (net (code "55") (name "Net-(D5-O5)") (class "Default")
      (node (ref "D5") (pin "14") (pinfunction "O5_14") (pintype "passive"))
      (node (ref "R17") (pin "1") (pinfunction "1_1") (pintype "passive"))
    )
    (net (code "56") (name "Net-(D5-O6)") (class "Default")
      (node (ref "D5") (pin "13") (pinfunction "O6_13") (pintype "passive"))
      (node (ref "R18") (pin "1") (pinfunction "1_1") (pintype "passive"))
    )
    (net (code "57") (name "Net-(D5-O7)") (class "Default")
      (node (ref "D5") (pin "12") (pinfunction "O7_12") (pintype "passive"))
      (node (ref "R19") (pin "1") (pinfunction "1_1") (pintype "passive"))
    )
    (net (code "58") (name "Net-(D6-Pad1)") (class "Default")
      (node (ref "D6") (pin "1") (pinfunction "1_1") (pintype "passive"))
      (node (ref "R9") (pin "2") (pinfunction "2_2") (pintype "passive"))
    )
    (net (code "59") (name "Net-(D6-Pad4)") (class "Default")
      (node (ref "D6") (pin "4") (pinfunction "4_4") (pintype "passive"))
      (node (ref "R10") (pin "2") (pinfunction "2_2") (pintype "passive"))
      (node (ref "R13") (pin "2") (pinfunction "2_2") (pintype "passive"))
    )
    (net (code "60") (name "Net-(D7-Pad1)") (class "Default")
      (node (ref "D7") (pin "1") (pinfunction "1_1") (pintype "passive"))
      (node (ref "R20") (pin "2") (pinfunction "2_2") (pintype "passive"))
    )
    (net (code "61") (name "Net-(D7-Pad4)") (class "Default")
      (node (ref "D7") (pin "4") (pinfunction "4_4") (pintype "passive"))
      (node (ref "R21") (pin "2") (pinfunction "2_2") (pintype "passive"))
      (node (ref "R22") (pin "2") (pinfunction "2_2") (pintype "passive"))
    )
    (net (code "62") (name "Net-(D8-O1)") (class "Default")
      (node (ref "D8") (pin "18") (pinfunction "O1_18") (pintype "passive"))
      (node (ref "R26") (pin "2") (pinfunction "2_2") (pintype "passive"))
    )
    (net (code "63") (name "Net-(D8-O2)") (class "Default")
      (node (ref "D8") (pin "17") (pinfunction "O2_17") (pintype "passive"))
      (node (ref "R27") (pin "2") (pinfunction "2_2") (pintype "passive"))
    )
    (net (code "64") (name "Net-(D8-O3)") (class "Default")
      (node (ref "D8") (pin "16") (pinfunction "O3_16") (pintype "passive"))
      (node (ref "R28") (pin "2") (pinfunction "2_2") (pintype "passive"))
    )
    (net (code "65") (name "Net-(D8-O4)") (class "Default")
      (node (ref "D8") (pin "15") (pinfunction "O4_15") (pintype "passive"))
      (node (ref "R29") (pin "2") (pinfunction "2_2") (pintype "passive"))
    )
    (net (code "66") (name "Net-(D8-O5)") (class "Default")
      (node (ref "D8") (pin "14") (pinfunction "O5_14") (pintype "passive"))
      (node (ref "R30") (pin "2") (pinfunction "2_2") (pintype "passive"))
    )
    (net (code "67") (name "Net-(D8-O6)") (class "Default")
      (node (ref "D8") (pin "13") (pinfunction "O6_13") (pintype "passive"))
      (node (ref "R31") (pin "2") (pinfunction "2_2") (pintype "passive"))
    )
    (net (code "68") (name "Net-(D8-O7)") (class "Default")
      (node (ref "D8") (pin "12") (pinfunction "O7_12") (pintype "passive"))
      (node (ref "R32") (pin "2") (pinfunction "2_2") (pintype "passive"))
    )
    (net (code "69") (name "Net-(D9-Pad1)") (class "Default")
      (node (ref "D9") (pin "1") (pinfunction "1_1") (pintype "passive"))
      (node (ref "R23") (pin "2") (pinfunction "2_2") (pintype "passive"))
    )
    (net (code "70") (name "Net-(D9-Pad4)") (class "Default")
      (node (ref "D9") (pin "4") (pinfunction "4_4") (pintype "passive"))
      (node (ref "R24") (pin "2") (pinfunction "2_2") (pintype "passive"))
      (node (ref "R25") (pin "2") (pinfunction "2_2") (pintype "passive"))
    )
    (net (code "71") (name "Net-(D10-Pad1)") (class "Default")
      (node (ref "D10") (pin "1") (pinfunction "1_1") (pintype "passive"))
      (node (ref "R33") (pin "2") (pinfunction "2_2") (pintype "passive"))
    )
    (net (code "72") (name "Net-(D10-Pad4)") (class "Default")
      (node (ref "D10") (pin "4") (pinfunction "4_4") (pintype "passive"))
      (node (ref "R34") (pin "2") (pinfunction "2_2") (pintype "passive"))
      (node (ref "R35") (pin "2") (pinfunction "2_2") (pintype "passive"))
    )
    (net (code "73") (name "Net-(D11-Pad1)") (class "Default")
      (node (ref "D11") (pin "1") (pinfunction "1_1") (pintype "passive"))
      (node (ref "R36") (pin "2") (pinfunction "2_2") (pintype "passive"))
    )
    (net (code "74") (name "Net-(D11-Pad4)") (class "Default")
      (node (ref "D11") (pin "4") (pinfunction "4_4") (pintype "passive"))
      (node (ref "R37") (pin "2") (pinfunction "2_2") (pintype "passive"))
      (node (ref "R38") (pin "2") (pinfunction "2_2") (pintype "passive"))
    )
    (net (code "75") (name "Net-(D12-Pad1)") (class "Default")
      (node (ref "D12") (pin "1") (pinfunction "1_1") (pintype "passive"))
      (node (ref "R39") (pin "2") (pinfunction "2_2") (pintype "passive"))
    )
    (net (code "76") (name "Net-(D12-Pad4)") (class "Default")
      (node (ref "D12") (pin "4") (pinfunction "4_4") (pintype "passive"))
      (node (ref "R40") (pin "2") (pinfunction "2_2") (pintype "passive"))
      (node (ref "R41") (pin "2") (pinfunction "2_2") (pintype "passive"))
    )
    (net (code "77") (name "Net-(R26-Pad1)") (class "Default")
      (node (ref "R26") (pin "1") (pinfunction "1_1") (pintype "passive"))
      (node (ref "XP5") (pin "10") (pinfunction "10_10") (pintype "passive"))
    )
    (net (code "78") (name "Net-(R27-Pad1)") (class "Default")
      (node (ref "R27") (pin "1") (pinfunction "1_1") (pintype "passive"))
      (node (ref "XP5") (pin "9") (pinfunction "9_9") (pintype "passive"))
    )
    (net (code "79") (name "Net-(R28-Pad1)") (class "Default")
      (node (ref "R28") (pin "1") (pinfunction "1_1") (pintype "passive"))
      (node (ref "XP5") (pin "8") (pinfunction "8_8") (pintype "passive"))
    )
    (net (code "80") (name "Net-(R29-Pad1)") (class "Default")
      (node (ref "R29") (pin "1") (pinfunction "1_1") (pintype "passive"))
      (node (ref "XP5") (pin "3") (pinfunction "3_3") (pintype "passive"))
    )
    (net (code "81") (name "Net-(R30-Pad1)") (class "Default")
      (node (ref "R30") (pin "1") (pinfunction "1_1") (pintype "passive"))
      (node (ref "XP5") (pin "2") (pinfunction "2_2") (pintype "passive"))
    )
    (net (code "82") (name "Net-(R31-Pad1)") (class "Default")
      (node (ref "R31") (pin "1") (pinfunction "1_1") (pintype "passive"))
      (node (ref "XP5") (pin "1") (pinfunction "1_1") (pintype "passive"))
    )
    (net (code "83") (name "Net-(R32-Pad1)") (class "Default")
      (node (ref "R32") (pin "1") (pinfunction "1_1") (pintype "passive"))
      (node (ref "XP5") (pin "4") (pinfunction "4_4") (pintype "passive"))
    )
    (net (code "84") (name "unconnected-(D5-I8-Pad8)") (class "Default")
      (node (ref "D5") (pin "8") (pinfunction "I8_8") (pintype "passive"))
    )
    (net (code "85") (name "unconnected-(D5-O8-Pad11)") (class "Default")
      (node (ref "D5") (pin "11") (pinfunction "O8_11") (pintype "passive"))
    )
    (net (code "86") (name "unconnected-(D8-I8-Pad8)") (class "Default")
      (node (ref "D8") (pin "8") (pinfunction "I8_8") (pintype "passive"))
    )
    (net (code "87") (name "unconnected-(D8-O8-Pad11)") (class "Default")
      (node (ref "D8") (pin "11") (pinfunction "O8_11") (pintype "passive"))
    )
    (net (code "88") (name "unconnected-(XP4-Pad17)") (class "Default")
      (node (ref "XP4") (pin "17") (pinfunction "17_17") (pintype "passive"))
    )
    (net (code "89") (name "unconnected-(XP4-Pad24)") (class "Default")
      (node (ref "XP4") (pin "24") (pinfunction "24_24") (pintype "passive"))
    )
    (net (code "90") (name "unconnected-(XP4-Pad26)") (class "Default")
      (node (ref "XP4") (pin "26") (pinfunction "26_26") (pintype "passive"))
    )
    (net (code "91") (name "unconnected-(XP4-Pad27)") (class "Default")
      (node (ref "XP4") (pin "27") (pinfunction "27_27") (pintype "passive"))
    )
    (net (code "92") (name "unconnected-(XP4-Pad28)") (class "Default")
      (node (ref "XP4") (pin "28") (pinfunction "28_28") (pintype "passive"))
    )
    (net (code "93") (name "unconnected-(XP4-Pad32)") (class "Default")
      (node (ref "XP4") (pin "32") (pinfunction "32_32") (pintype "passive"))
    )
    (net (code "94") (name "unconnected-(XP5-Pad6)") (class "Default")
      (node (ref "XP5") (pin "6") (pinfunction "6_6") (pintype "passive"))
    )
    (net (code "95") (name "unconnected-(XP5-Pad7)") (class "Default")
      (node (ref "XP5") (pin "7") (pinfunction "7_7") (pintype "passive"))
    )
  )
)
